# Programmieradapter.net
KiCad netlist of a schematic drawn in EAGLE
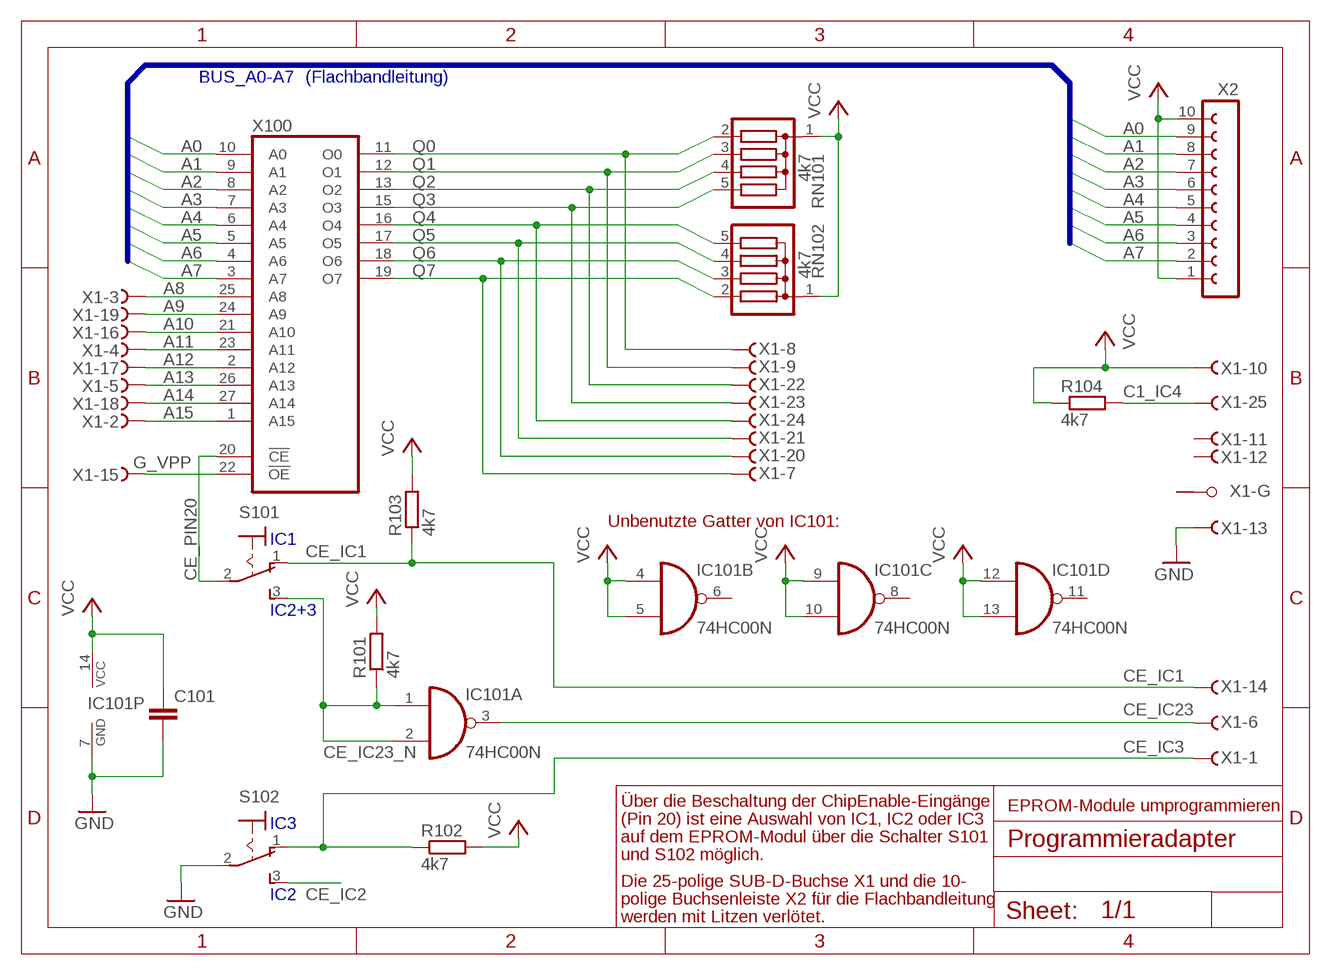
[diagram p0: schematic, sheet 1]

(export (version "E")
  (design (tool "Eeschema 10.0.6"))
  (components
    (comp (ref "C101")
      (value "C-EU050-024X044")
      (footprint "eagle-import:C050-024X044")
      (libsource (lib "eagle-import") (part "C-EU050-024X044"))
    )
    (comp (ref "IC101")
      (value "74HC00N")
      (footprint "eagle-import:DIL14")
      (libsource (lib "eagle-import") (part "7400NHC"))
    )
    (comp (ref "R101")
      (value "4k7")
      (footprint "eagle-import:0207_10")
      (libsource (lib "eagle-import") (part "R-EU_0207/10"))
    )
    (comp (ref "R102")
      (value "4k7")
      (footprint "eagle-import:0207_10")
      (libsource (lib "eagle-import") (part "R-EU_0207/10"))
    )
    (comp (ref "R103")
      (value "4k7")
      (footprint "eagle-import:0207_10")
      (libsource (lib "eagle-import") (part "R-EU_0207/10"))
    )
    (comp (ref "R104")
      (value "4k7")
      (footprint "eagle-import:0207_10")
      (libsource (lib "eagle-import") (part "R-EU_0207/10"))
    )
    (comp (ref "RN101")
      (value "4k7")
      (footprint "eagle-import:SIL5")
      (libsource (lib "eagle-import") (part "G04R"))
    )
    (comp (ref "RN102")
      (value "4k7")
      (footprint "eagle-import:SIL5")
      (libsource (lib "eagle-import") (part "G04R"))
    )
    (comp (ref "S101")
      (value "320-916")
      (footprint "eagle-import:320-916")
      (libsource (lib "eagle-import") (part "320-916"))
    )
    (comp (ref "S102")
      (value "320-916")
      (footprint "eagle-import:320-916")
      (libsource (lib "eagle-import") (part "320-916"))
    )
    (comp (ref "X1")
      (value "F25VPS")
      (footprint "eagle-import:F25VP")
      (libsource (lib "eagle-import") (part "F25VPS"))
    )
    (comp (ref "X2")
      (value "FE10-1")
      (footprint "eagle-import:FE10")
      (libsource (lib "eagle-import") (part "FE10-1"))
    )
    (comp (ref "X100")
      (value "27512")
      (footprint "eagle-import:DIL28")
      (libsource (lib "eagle-import") (part "27512"))
    )
  )
  (nets
    (net (code "2") (name "/A0") (class "Default")
      (node (ref "X100") (pin "10") (pinfunction "A0_10") (pintype "input"))
      (node (ref "X2") (pin "9") (pinfunction "9_9") (pintype "passive"))
    )
    (net (code "3") (name "/A1") (class "Default")
      (node (ref "X100") (pin "9") (pinfunction "A1_9") (pintype "input"))
      (node (ref "X2") (pin "8") (pinfunction "8_8") (pintype "passive"))
    )
    (net (code "4") (name "/A2") (class "Default")
      (node (ref "X100") (pin "8") (pinfunction "A2_8") (pintype "input"))
      (node (ref "X2") (pin "7") (pinfunction "7_7") (pintype "passive"))
    )
    (net (code "5") (name "/A3") (class "Default")
      (node (ref "X100") (pin "7") (pinfunction "A3_7") (pintype "input"))
      (node (ref "X2") (pin "6") (pinfunction "6_6") (pintype "passive"))
    )
    (net (code "6") (name "/A4") (class "Default")
      (node (ref "X100") (pin "6") (pinfunction "A4_6") (pintype "input"))
      (node (ref "X2") (pin "5") (pinfunction "5_5") (pintype "passive"))
    )
    (net (code "7") (name "/A5") (class "Default")
      (node (ref "X100") (pin "5") (pinfunction "A5_5") (pintype "input"))
      (node (ref "X2") (pin "4") (pinfunction "4_4") (pintype "passive"))
    )
    (net (code "8") (name "/A6") (class "Default")
      (node (ref "X100") (pin "4") (pinfunction "A6_4") (pintype "input"))
      (node (ref "X2") (pin "3") (pinfunction "3_3") (pintype "passive"))
    )
    (net (code "9") (name "/A7") (class "Default")
      (node (ref "X100") (pin "3") (pinfunction "A7_3") (pintype "input"))
      (node (ref "X2") (pin "2") (pinfunction "2_2") (pintype "passive"))
    )
    (net (code "10") (name "/A8") (class "Default")
      (node (ref "X1") (pin "3") (pinfunction "F_3") (pintype "passive"))
      (node (ref "X100") (pin "25") (pinfunction "A8_25") (pintype "input"))
    )
    (net (code "11") (name "/A9") (class "Default")
      (node (ref "X1") (pin "19") (pinfunction "F_19") (pintype "passive"))
      (node (ref "X100") (pin "24") (pinfunction "A9_24") (pintype "input"))
    )
    (net (code "12") (name "/A10") (class "Default")
      (node (ref "X1") (pin "16") (pinfunction "F_16") (pintype "passive"))
      (node (ref "X100") (pin "21") (pinfunction "A10_21") (pintype "input"))
    )
    (net (code "13") (name "/A11") (class "Default")
      (node (ref "X1") (pin "4") (pinfunction "F_4") (pintype "passive"))
      (node (ref "X100") (pin "23") (pinfunction "A11_23") (pintype "input"))
    )
    (net (code "14") (name "/A12") (class "Default")
      (node (ref "X1") (pin "17") (pinfunction "F_17") (pintype "passive"))
      (node (ref "X100") (pin "2") (pinfunction "A12_2") (pintype "input"))
    )
    (net (code "15") (name "/A13") (class "Default")
      (node (ref "X1") (pin "5") (pinfunction "F_5") (pintype "passive"))
      (node (ref "X100") (pin "26") (pinfunction "A13_26") (pintype "input"))
    )
    (net (code "16") (name "/A14") (class "Default")
      (node (ref "X1") (pin "18") (pinfunction "F_18") (pintype "passive"))
      (node (ref "X100") (pin "27") (pinfunction "A14_27") (pintype "input"))
    )
    (net (code "17") (name "/A15") (class "Default")
      (node (ref "X1") (pin "2") (pinfunction "F_2") (pintype "passive"))
      (node (ref "X100") (pin "1") (pinfunction "A15_1") (pintype "input"))
    )
    (net (code "18") (name "/C1_IC4") (class "Default")
      (node (ref "R104") (pin "2") (pinfunction "2_2") (pintype "passive"))
      (node (ref "X1") (pin "25") (pinfunction "F_25") (pintype "passive"))
    )
    (net (code "19") (name "/CE_IC1") (class "Default")
      (node (ref "R103") (pin "1") (pinfunction "1_1") (pintype "passive"))
      (node (ref "S101") (pin "1") (pinfunction "O_1") (pintype "passive"))
      (node (ref "X1") (pin "14") (pinfunction "F_14") (pintype "passive"))
    )
    (net (code "20") (name "/CE_IC2") (class "Default")
      (node (ref "S102") (pin "3") (pinfunction "S_3") (pintype "passive"))
    )
    (net (code "21") (name "/CE_IC3") (class "Default")
      (node (ref "R102") (pin "1") (pinfunction "1_1") (pintype "passive"))
      (node (ref "S102") (pin "1") (pinfunction "O_1") (pintype "passive"))
      (node (ref "X1") (pin "1") (pinfunction "F_1") (pintype "passive"))
    )
    (net (code "22") (name "/CE_IC23") (class "Default")
      (node (ref "IC101") (pin "3") (pinfunction "O_3") (pintype "output"))
      (node (ref "X1") (pin "6") (pinfunction "F_6") (pintype "passive"))
    )
    (net (code "23") (name "/CE_IC23_N") (class "Default")
      (node (ref "IC101") (pin "1") (pinfunction "I0_1") (pintype "input"))
      (node (ref "IC101") (pin "2") (pinfunction "I1_2") (pintype "input"))
      (node (ref "R101") (pin "1") (pinfunction "1_1") (pintype "passive"))
      (node (ref "S101") (pin "3") (pinfunction "S_3") (pintype "passive"))
    )
    (net (code "24") (name "/CE_PIN20") (class "Default")
      (node (ref "S101") (pin "2") (pinfunction "P_2") (pintype "passive"))
      (node (ref "X100") (pin "20") (pinfunction "~{CE}_20") (pintype "input"))
    )
    (net (code "25") (name "/G_VPP") (class "Default")
      (node (ref "X1") (pin "15") (pinfunction "F_15") (pintype "passive"))
      (node (ref "X100") (pin "22") (pinfunction "~{OE}_22") (pintype "input"))
    )
    (net (code "26") (name "/Q0") (class "Default")
      (node (ref "RN101") (pin "2") (pinfunction "2_2") (pintype "passive"))
      (node (ref "X1") (pin "8") (pinfunction "F_8") (pintype "passive"))
      (node (ref "X100") (pin "11") (pinfunction "O0_11") (pintype "tri_state"))
    )
    (net (code "27") (name "/Q1") (class "Default")
      (node (ref "RN101") (pin "3") (pinfunction "3_3") (pintype "passive"))
      (node (ref "X1") (pin "9") (pinfunction "F_9") (pintype "passive"))
      (node (ref "X100") (pin "12") (pinfunction "O1_12") (pintype "tri_state"))
    )
    (net (code "28") (name "/Q2") (class "Default")
      (node (ref "RN101") (pin "4") (pinfunction "4_4") (pintype "passive"))
      (node (ref "X1") (pin "22") (pinfunction "F_22") (pintype "passive"))
      (node (ref "X100") (pin "13") (pinfunction "O2_13") (pintype "tri_state"))
    )
    (net (code "29") (name "/Q3") (class "Default")
      (node (ref "RN101") (pin "5") (pinfunction "5_5") (pintype "passive"))
      (node (ref "X1") (pin "23") (pinfunction "F_23") (pintype "passive"))
      (node (ref "X100") (pin "15") (pinfunction "O3_15") (pintype "tri_state"))
    )
    (net (code "30") (name "/Q4") (class "Default")
      (node (ref "RN102") (pin "5") (pinfunction "5_5") (pintype "passive"))
      (node (ref "X1") (pin "24") (pinfunction "F_24") (pintype "passive"))
      (node (ref "X100") (pin "16") (pinfunction "O4_16") (pintype "tri_state"))
    )
    (net (code "31") (name "/Q5") (class "Default")
      (node (ref "RN102") (pin "4") (pinfunction "4_4") (pintype "passive"))
      (node (ref "X1") (pin "21") (pinfunction "F_21") (pintype "passive"))
      (node (ref "X100") (pin "17") (pinfunction "O5_17") (pintype "tri_state"))
    )
    (net (code "32") (name "/Q6") (class "Default")
      (node (ref "RN102") (pin "3") (pinfunction "3_3") (pintype "passive"))
      (node (ref "X1") (pin "20") (pinfunction "F_20") (pintype "passive"))
      (node (ref "X100") (pin "18") (pinfunction "O6_18") (pintype "tri_state"))
    )
    (net (code "33") (name "/Q7") (class "Default")
      (node (ref "RN102") (pin "2") (pinfunction "2_2") (pintype "passive"))
      (node (ref "X1") (pin "7") (pinfunction "F_7") (pintype "passive"))
      (node (ref "X100") (pin "19") (pinfunction "O7_19") (pintype "tri_state"))
    )
    (net (code "35") (name "GND") (class "Default")
      (node (ref "C101") (pin "2") (pinfunction "2_2") (pintype "passive"))
      (node (ref "IC101") (pin "7") (pinfunction "GND_7") (pintype "power_in"))
      (node (ref "S102") (pin "2") (pinfunction "P_2") (pintype "passive"))
      (node (ref "X1") (pin "13") (pinfunction "F_13") (pintype "passive"))
    )
    (net (code "36") (name "VCC") (class "Default")
      (node (ref "C101") (pin "1") (pinfunction "1_1") (pintype "passive"))
      (node (ref "IC101") (pin "10") (pinfunction "I1_10") (pintype "input"))
      (node (ref "IC101") (pin "12") (pinfunction "I0_12") (pintype "input"))
      (node (ref "IC101") (pin "13") (pinfunction "I1_13") (pintype "input"))
      (node (ref "IC101") (pin "14") (pinfunction "VCC_14") (pintype "power_in"))
      (node (ref "IC101") (pin "4") (pinfunction "I0_4") (pintype "input"))
      (node (ref "IC101") (pin "5") (pinfunction "I1_5") (pintype "input"))
      (node (ref "IC101") (pin "9") (pinfunction "I0_9") (pintype "input"))
      (node (ref "R101") (pin "2") (pinfunction "2_2") (pintype "passive"))
      (node (ref "R102") (pin "2") (pinfunction "2_2") (pintype "passive"))
      (node (ref "R103") (pin "2") (pinfunction "2_2") (pintype "passive"))
      (node (ref "R104") (pin "1") (pinfunction "1_1") (pintype "passive"))
      (node (ref "RN101") (pin "1") (pinfunction "1_1") (pintype "passive"))
      (node (ref "RN102") (pin "1") (pinfunction "1_1") (pintype "passive"))
      (node (ref "X1") (pin "10") (pinfunction "F_10") (pintype "passive"))
      (node (ref "X2") (pin "1") (pinfunction "1_1") (pintype "passive"))
      (node (ref "X2") (pin "10") (pinfunction "10_10") (pintype "passive"))
    )
    (net (code "37") (name "unconnected-(IC101B-O-Pad6)") (class "Default")
      (node (ref "IC101") (pin "6") (pinfunction "O_6") (pintype "output"))
    )
    (net (code "38") (name "unconnected-(IC101C-O-Pad8)") (class "Default")
      (node (ref "IC101") (pin "8") (pinfunction "O_8") (pintype "output"))
    )
    (net (code "39") (name "unconnected-(IC101D-O-Pad11)") (class "Default")
      (node (ref "IC101") (pin "11") (pinfunction "O_11") (pintype "output"))
    )
    (net (code "40") (name "unconnected-(X1-PadG1)") (class "Default")
      (node (ref "X1") (pin "G1") (pinfunction "G1_G1") (pintype "passive"))
    )
    (net (code "41") (name "unconnected-(X1-PadG2)") (class "Default")
      (node (ref "X1") (pin "G2") (pinfunction "G2_G2") (pintype "passive"))
    )
    (net (code "42") (name "unconnected-(X1C-F-Pad11)") (class "Default")
      (node (ref "X1") (pin "11") (pinfunction "F_11") (pintype "passive"))
    )
    (net (code "43") (name "unconnected-(X1D-F-Pad12)") (class "Default")
      (node (ref "X1") (pin "12") (pinfunction "F_12") (pintype "passive"))
    )
  )
)
